# MICROSD.net
KiCad netlist of a schematic drawn in Altium Designer
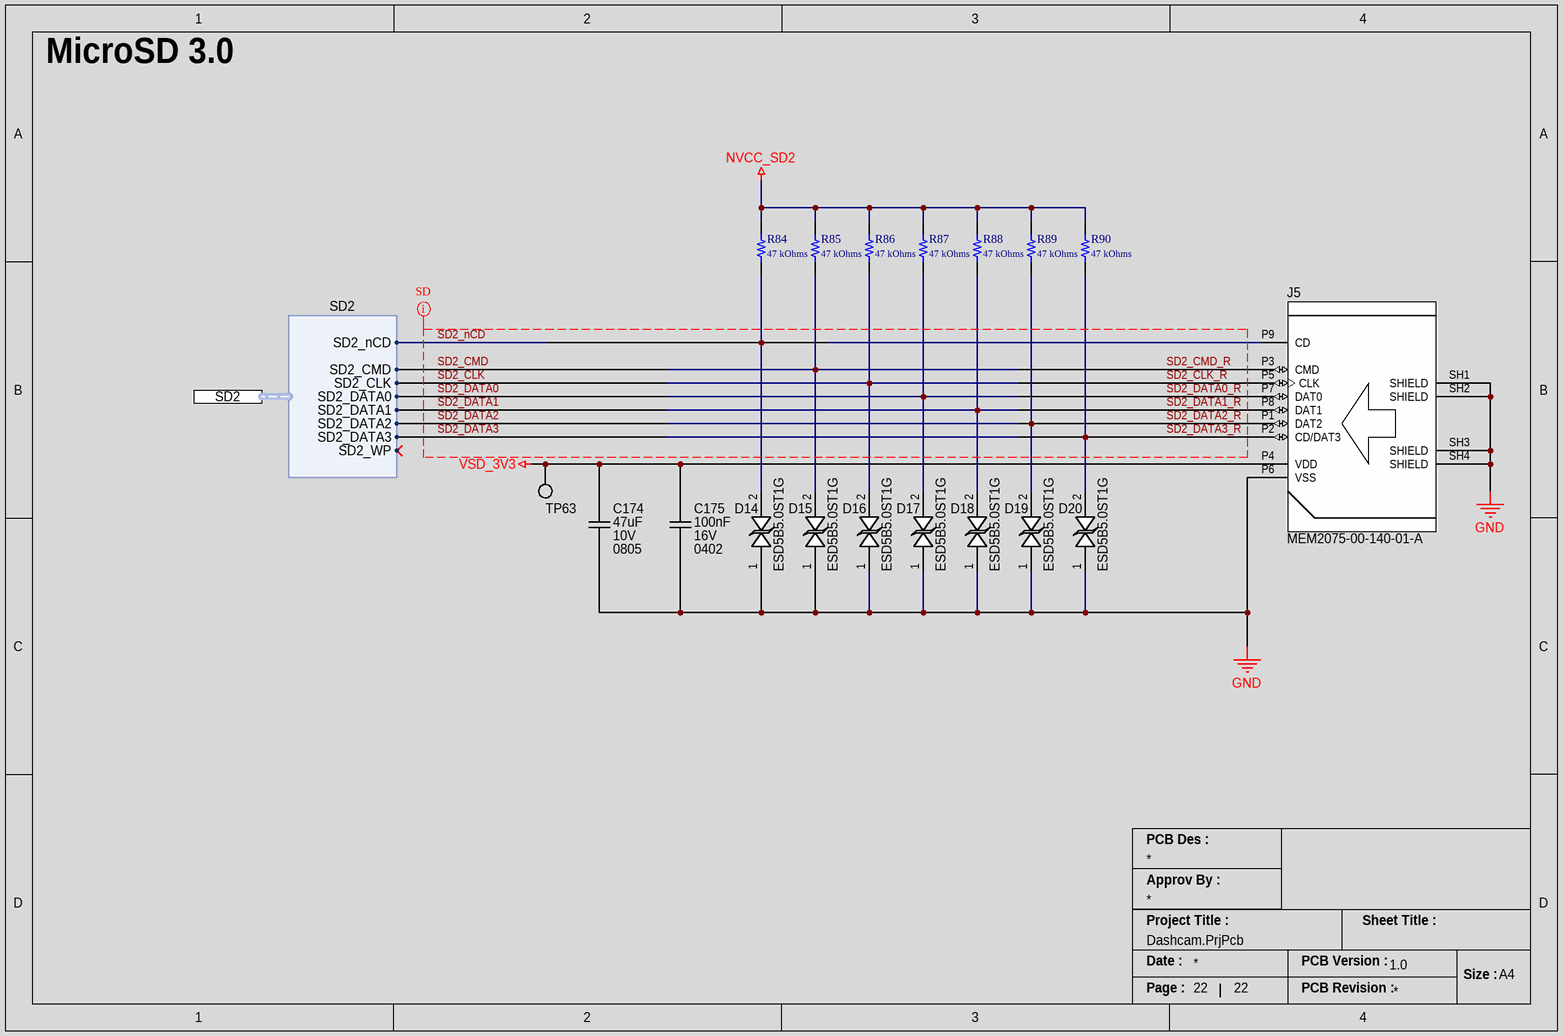
[diagram p0: MICROSD.SchDoc]

(export (version "E")
  (design (tool "Eeschema 10.0.6"))
  (components
    (comp (ref "C174")
      (value "C2012X5R1A476M125AC")
      (footprint "CAP_0805_CAPC2012X12N")
      (description "Multilayer Ceramic Capacitor, 47 uF, 10 V, ± 20%, X5R, 0805 [2012 Metric]")
      (fields
        (field (name "MANUFACTURER") "TDK")
        (field (name "TOLERANCE") "20%")
        (field (name "VOLTAGE RATING (DC)") "10V")
        (field (name "CAPACITANCE") "47uF")
        (field (name "CASE CODE (IMPERIAL)") "0805")
      )
      (libsource (lib "Electronic Devices_LIB") (part "CAP_47UF_10V_X5R_0805"))
    )
    (comp (ref "C175")
      (value "CL05B104KO5NNNC")
      (footprint "CAP_0402_CAPC1005X05N")
      (description "Multilayer Ceramic Capacitor, 0.1 uF, 16 V, ± 10%, X7R, 0402 [1005 Metric]")
      (fields
        (field (name "MANUFACTURER") "Samsung")
        (field (name "TOLERANCE") "10%")
        (field (name "VOLTAGE RATING") "16V")
        (field (name "CAPACITANCE") "100nF")
        (field (name "CASE/PACKAGE") "0402")
      )
      (libsource (lib "Electronic Devices_LIB") (part "CAP_100NF_16V_X7R_0402"))
    )
    (comp (ref "D14")
      (value "ESD5B5.0ST1G")
      (footprint "DIO_TVS_SODFL1608X70N")
      (description "ESD5B5.0S Series 5.8 V 50 W 32 pF SMT ESD Protection Diode - SOD-523")
      (libsource (lib "Electronic Devices_LIB") (part "DIO_TVS_5.8V_ESD5B5.0ST1G_1"))
    )
    (comp (ref "D15")
      (value "ESD5B5.0ST1G")
      (footprint "DIO_TVS_SODFL1608X70N")
      (description "ESD5B5.0S Series 5.8 V 50 W 32 pF SMT ESD Protection Diode - SOD-523")
      (libsource (lib "Electronic Devices_LIB") (part "DIO_TVS_5.8V_ESD5B5.0ST1G_1"))
    )
    (comp (ref "D16")
      (value "ESD5B5.0ST1G")
      (footprint "DIO_TVS_SODFL1608X70N")
      (description "ESD5B5.0S Series 5.8 V 50 W 32 pF SMT ESD Protection Diode - SOD-523")
      (libsource (lib "Electronic Devices_LIB") (part "DIO_TVS_5.8V_ESD5B5.0ST1G_1"))
    )
    (comp (ref "D17")
      (value "ESD5B5.0ST1G")
      (footprint "DIO_TVS_SODFL1608X70N")
      (description "ESD5B5.0S Series 5.8 V 50 W 32 pF SMT ESD Protection Diode - SOD-523")
      (libsource (lib "Electronic Devices_LIB") (part "DIO_TVS_5.8V_ESD5B5.0ST1G_1"))
    )
    (comp (ref "D18")
      (value "ESD5B5.0ST1G")
      (footprint "DIO_TVS_SODFL1608X70N")
      (description "ESD5B5.0S Series 5.8 V 50 W 32 pF SMT ESD Protection Diode - SOD-523")
      (libsource (lib "Electronic Devices_LIB") (part "DIO_TVS_5.8V_ESD5B5.0ST1G_1"))
    )
    (comp (ref "D19")
      (value "ESD5B5.0ST1G")
      (footprint "DIO_TVS_SODFL1608X70N")
      (description "ESD5B5.0S Series 5.8 V 50 W 32 pF SMT ESD Protection Diode - SOD-523")
      (libsource (lib "Electronic Devices_LIB") (part "DIO_TVS_5.8V_ESD5B5.0ST1G_1"))
    )
    (comp (ref "D20")
      (value "ESD5B5.0ST1G")
      (footprint "DIO_TVS_SODFL1608X70N")
      (description "ESD5B5.0S Series 5.8 V 50 W 32 pF SMT ESD Protection Diode - SOD-523")
      (libsource (lib "Electronic Devices_LIB") (part "DIO_TVS_5.8V_ESD5B5.0ST1G_1"))
    )
    (comp (ref "J5")
      (value "MEM2075-00-140-01-A")
      (footprint "CONN_MICROSD_GCT_MEM2075-00-140-01-A")
      (description "Memory Card Connectors Micro SD Push-Push, SMT, 1.40mm Profile, With Peg, Open Switch, T&R")
      (fields (field (name "MANUFACTURER") "Global Connector Technology"))
      (libsource (lib "Electronic Devices_LIB") (part "CONN_MICROSD_MEM2075-00-140-01-A"))
    )
    (comp (ref "R84")
      (value "47 kOhms")
      (footprint "YAGEO RES 0402_1005")
      (description "RES SMD 47K OHM 5% 1/16W 0402")
      (fields (field (name "PART NUMBER") "AC0402JR-0747KL") (field (name "MANUFACTURER") "Yageo"))
      (libsource (lib "Celestial Altium Library - altium_library") (part "Resistor"))
    )
    (comp (ref "R85")
      (value "47 kOhms")
      (footprint "YAGEO RES 0402_1005")
      (description "RES SMD 47K OHM 5% 1/16W 0402")
      (fields (field (name "PART NUMBER") "AC0402JR-0747KL") (field (name "MANUFACTURER") "Yageo"))
      (libsource (lib "Celestial Altium Library - altium_library") (part "Resistor"))
    )
    (comp (ref "R86")
      (value "47 kOhms")
      (footprint "YAGEO RES 0402_1005")
      (description "RES SMD 47K OHM 5% 1/16W 0402")
      (fields (field (name "PART NUMBER") "AC0402JR-0747KL") (field (name "MANUFACTURER") "Yageo"))
      (libsource (lib "Celestial Altium Library - altium_library") (part "Resistor"))
    )
    (comp (ref "R87")
      (value "47 kOhms")
      (footprint "YAGEO RES 0402_1005")
      (description "RES SMD 47K OHM 5% 1/16W 0402")
      (fields (field (name "PART NUMBER") "AC0402JR-0747KL") (field (name "MANUFACTURER") "Yageo"))
      (libsource (lib "Celestial Altium Library - altium_library") (part "Resistor"))
    )
    (comp (ref "R88")
      (value "47 kOhms")
      (footprint "YAGEO RES 0402_1005")
      (description "RES SMD 47K OHM 5% 1/16W 0402")
      (fields (field (name "PART NUMBER") "AC0402JR-0747KL") (field (name "MANUFACTURER") "Yageo"))
      (libsource (lib "Celestial Altium Library - altium_library") (part "Resistor"))
    )
    (comp (ref "R89")
      (value "47 kOhms")
      (footprint "YAGEO RES 0402_1005")
      (description "RES SMD 47K OHM 5% 1/16W 0402")
      (fields (field (name "PART NUMBER") "AC0402JR-0747KL") (field (name "MANUFACTURER") "Yageo"))
      (libsource (lib "Celestial Altium Library - altium_library") (part "Resistor"))
    )
    (comp (ref "R90")
      (value "47 kOhms")
      (footprint "YAGEO RES 0402_1005")
      (description "RES SMD 47K OHM 5% 1/16W 0402")
      (fields (field (name "PART NUMBER") "AC0402JR-0747KL") (field (name "MANUFACTURER") "Yageo"))
      (libsource (lib "Celestial Altium Library - altium_library") (part "Resistor"))
    )
    (comp (ref "TP63")
      (value "NO COMPONENT")
      (footprint "TP_PAD_0.5MM_SMD_ROUND")
      (description "Test Point, SMD pad, round, 1.5mm, 1.6mm, 3mm diameter")
      (libsource (lib "Electronic Devices_LIB") (part "TP_PAD_SMD_SMALL"))
    )
  )
  (nets
    (net (code "2") (name "/SD2_CLK") (class "Default")
      (node (ref "D16") (pin "2") (pinfunction "A2_2") (pintype "passive"))
      (node (ref "J5") (pin "P5") (pinfunction "CLK_P5") (pintype "bidirectional"))
      (node (ref "R86") (pin "1") (pinfunction "1_1") (pintype "passive"))
    )
    (net (code "3") (name "/SD2_CMD") (class "Default")
      (node (ref "D15") (pin "2") (pinfunction "A2_2") (pintype "passive"))
      (node (ref "J5") (pin "P3") (pinfunction "CMD_P3") (pintype "bidirectional"))
      (node (ref "R85") (pin "1") (pinfunction "1_1") (pintype "passive"))
    )
    (net (code "4") (name "/SD2_DATA0") (class "Default")
      (node (ref "D17") (pin "2") (pinfunction "A2_2") (pintype "passive"))
      (node (ref "J5") (pin "P7") (pinfunction "DAT0_P7") (pintype "bidirectional"))
      (node (ref "R87") (pin "1") (pinfunction "1_1") (pintype "passive"))
    )
    (net (code "5") (name "/SD2_DATA1") (class "Default")
      (node (ref "D18") (pin "2") (pinfunction "A2_2") (pintype "passive"))
      (node (ref "J5") (pin "P8") (pinfunction "DAT1_P8") (pintype "bidirectional"))
      (node (ref "R88") (pin "1") (pinfunction "1_1") (pintype "passive"))
    )
    (net (code "6") (name "/SD2_DATA2") (class "Default")
      (node (ref "D19") (pin "2") (pinfunction "A2_2") (pintype "passive"))
      (node (ref "J5") (pin "P1") (pinfunction "DAT2_P1") (pintype "bidirectional"))
      (node (ref "R89") (pin "1") (pinfunction "1_1") (pintype "passive"))
    )
    (net (code "7") (name "/SD2_DATA3") (class "Default")
      (node (ref "D20") (pin "2") (pinfunction "A2_2") (pintype "passive"))
      (node (ref "J5") (pin "P2") (pinfunction "CD/DAT3_P2") (pintype "bidirectional"))
      (node (ref "R90") (pin "1") (pinfunction "1_1") (pintype "passive"))
    )
    (net (code "8") (name "/SD2_nCD") (class "Default")
      (node (ref "D14") (pin "2") (pinfunction "A2_2") (pintype "passive"))
      (node (ref "J5") (pin "P9") (pinfunction "CD_P9") (pintype "passive"))
      (node (ref "R84") (pin "1") (pinfunction "1_1") (pintype "passive"))
    )
    (net (code "10") (name "GND") (class "Default")
      (node (ref "C174") (pin "1") (pinfunction "1_1") (pintype "passive"))
      (node (ref "C175") (pin "1") (pinfunction "1_1") (pintype "passive"))
      (node (ref "D14") (pin "1") (pinfunction "A1_1") (pintype "passive"))
      (node (ref "D15") (pin "1") (pinfunction "A1_1") (pintype "passive"))
      (node (ref "D16") (pin "1") (pinfunction "A1_1") (pintype "passive"))
      (node (ref "D17") (pin "1") (pinfunction "A1_1") (pintype "passive"))
      (node (ref "D18") (pin "1") (pinfunction "A1_1") (pintype "passive"))
      (node (ref "D19") (pin "1") (pinfunction "A1_1") (pintype "passive"))
      (node (ref "D20") (pin "1") (pinfunction "A1_1") (pintype "passive"))
      (node (ref "J5") (pin "P6") (pinfunction "VSS_P6") (pintype "power_in"))
      (node (ref "J5") (pin "SH1") (pinfunction "SHIELD_SH1") (pintype "power_in"))
      (node (ref "J5") (pin "SH2") (pinfunction "SHIELD_SH2") (pintype "power_in"))
      (node (ref "J5") (pin "SH3") (pinfunction "SHIELD_SH3") (pintype "power_in"))
      (node (ref "J5") (pin "SH4") (pinfunction "SHIELD_SH4") (pintype "power_in"))
    )
    (net (code "11") (name "NVCC_SD2") (class "Default")
      (node (ref "R84") (pin "2") (pinfunction "2_2") (pintype "passive"))
      (node (ref "R85") (pin "2") (pinfunction "2_2") (pintype "passive"))
      (node (ref "R86") (pin "2") (pinfunction "2_2") (pintype "passive"))
      (node (ref "R87") (pin "2") (pinfunction "2_2") (pintype "passive"))
      (node (ref "R88") (pin "2") (pinfunction "2_2") (pintype "passive"))
      (node (ref "R89") (pin "2") (pinfunction "2_2") (pintype "passive"))
      (node (ref "R90") (pin "2") (pinfunction "2_2") (pintype "passive"))
    )
    (net (code "12") (name "VSD_3V3") (class "Default")
      (node (ref "C174") (pin "2") (pinfunction "2_2") (pintype "passive"))
      (node (ref "C175") (pin "2") (pinfunction "2_2") (pintype "passive"))
      (node (ref "J5") (pin "P4") (pinfunction "VDD_P4") (pintype "power_in"))
      (node (ref "TP63") (pin "1") (pinfunction "1_1") (pintype "passive"))
    )
  )
)
